# Keys.net
KiCad netlist of a schematic drawn in Altium Designer
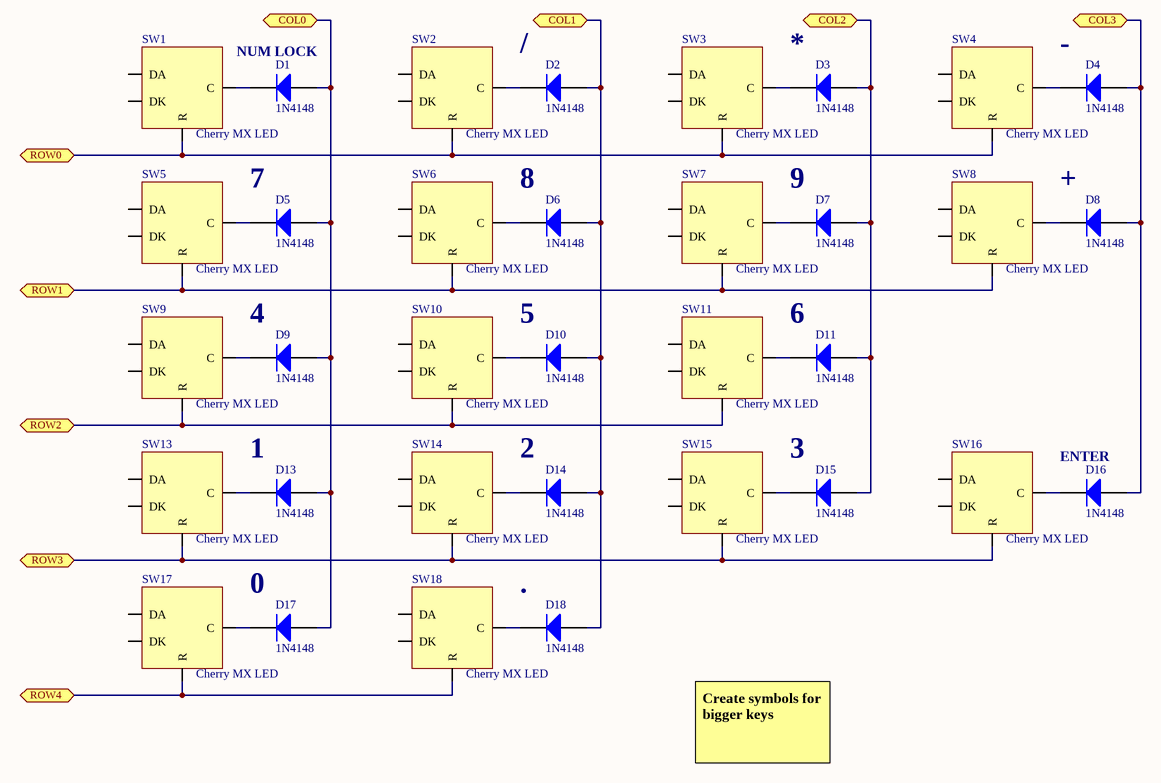
[diagram p0: Keys.SchDoc]

(export (version "E")
  (design (tool "Eeschema 10.0.6"))
  (components
    (comp (ref "D1")
      (value "1N4148")
      (footprint "NXP-SOD27-2_V")
      (description "High-speed Diode, 100 V, 450 mA, 2-Pin SOD27, RoHS")
      (fields (field (name "MANUFACTURER") "NXP Semiconductors"))
      (libsource (lib "Altium Content Vault") (part "NXP-A1K2-2"))
    )
    (comp (ref "D2")
      (value "1N4148")
      (footprint "NXP-SOD27-2_V")
      (description "High-speed Diode, 100 V, 450 mA, 2-Pin SOD27, RoHS")
      (fields (field (name "MANUFACTURER") "NXP Semiconductors"))
      (libsource (lib "Altium Content Vault") (part "NXP-A1K2-2"))
    )
    (comp (ref "D3")
      (value "1N4148")
      (footprint "NXP-SOD27-2_V")
      (description "High-speed Diode, 100 V, 450 mA, 2-Pin SOD27, RoHS")
      (fields (field (name "MANUFACTURER") "NXP Semiconductors"))
      (libsource (lib "Altium Content Vault") (part "NXP-A1K2-2"))
    )
    (comp (ref "D4")
      (value "1N4148")
      (footprint "NXP-SOD27-2_V")
      (description "High-speed Diode, 100 V, 450 mA, 2-Pin SOD27, RoHS")
      (fields (field (name "MANUFACTURER") "NXP Semiconductors"))
      (libsource (lib "Altium Content Vault") (part "NXP-A1K2-2"))
    )
    (comp (ref "D5")
      (value "1N4148")
      (footprint "NXP-SOD27-2_V")
      (description "High-speed Diode, 100 V, 450 mA, 2-Pin SOD27, RoHS")
      (fields (field (name "MANUFACTURER") "NXP Semiconductors"))
      (libsource (lib "Altium Content Vault") (part "NXP-A1K2-2"))
    )
    (comp (ref "D6")
      (value "1N4148")
      (footprint "NXP-SOD27-2_V")
      (description "High-speed Diode, 100 V, 450 mA, 2-Pin SOD27, RoHS")
      (fields (field (name "MANUFACTURER") "NXP Semiconductors"))
      (libsource (lib "Altium Content Vault") (part "NXP-A1K2-2"))
    )
    (comp (ref "D7")
      (value "1N4148")
      (footprint "NXP-SOD27-2_V")
      (description "High-speed Diode, 100 V, 450 mA, 2-Pin SOD27, RoHS")
      (fields (field (name "MANUFACTURER") "NXP Semiconductors"))
      (libsource (lib "Altium Content Vault") (part "NXP-A1K2-2"))
    )
    (comp (ref "D8")
      (value "1N4148")
      (footprint "NXP-SOD27-2_V")
      (description "High-speed Diode, 100 V, 450 mA, 2-Pin SOD27, RoHS")
      (fields (field (name "MANUFACTURER") "NXP Semiconductors"))
      (libsource (lib "Altium Content Vault") (part "NXP-A1K2-2"))
    )
    (comp (ref "D9")
      (value "1N4148")
      (footprint "NXP-SOD27-2_V")
      (description "High-speed Diode, 100 V, 450 mA, 2-Pin SOD27, RoHS")
      (fields (field (name "MANUFACTURER") "NXP Semiconductors"))
      (libsource (lib "Altium Content Vault") (part "NXP-A1K2-2"))
    )
    (comp (ref "D10")
      (value "1N4148")
      (footprint "NXP-SOD27-2_V")
      (description "High-speed Diode, 100 V, 450 mA, 2-Pin SOD27, RoHS")
      (fields (field (name "MANUFACTURER") "NXP Semiconductors"))
      (libsource (lib "Altium Content Vault") (part "NXP-A1K2-2"))
    )
    (comp (ref "D11")
      (value "1N4148")
      (footprint "NXP-SOD27-2_V")
      (description "High-speed Diode, 100 V, 450 mA, 2-Pin SOD27, RoHS")
      (fields (field (name "MANUFACTURER") "NXP Semiconductors"))
      (libsource (lib "Altium Content Vault") (part "NXP-A1K2-2"))
    )
    (comp (ref "D13")
      (value "1N4148")
      (footprint "NXP-SOD27-2_V")
      (description "High-speed Diode, 100 V, 450 mA, 2-Pin SOD27, RoHS")
      (fields (field (name "MANUFACTURER") "NXP Semiconductors"))
      (libsource (lib "Altium Content Vault") (part "NXP-A1K2-2"))
    )
    (comp (ref "D14")
      (value "1N4148")
      (footprint "NXP-SOD27-2_V")
      (description "High-speed Diode, 100 V, 450 mA, 2-Pin SOD27, RoHS")
      (fields (field (name "MANUFACTURER") "NXP Semiconductors"))
      (libsource (lib "Altium Content Vault") (part "NXP-A1K2-2"))
    )
    (comp (ref "D15")
      (value "1N4148")
      (footprint "NXP-SOD27-2_V")
      (description "High-speed Diode, 100 V, 450 mA, 2-Pin SOD27, RoHS")
      (fields (field (name "MANUFACTURER") "NXP Semiconductors"))
      (libsource (lib "Altium Content Vault") (part "NXP-A1K2-2"))
    )
    (comp (ref "D16")
      (value "1N4148")
      (footprint "NXP-SOD27-2_V")
      (description "High-speed Diode, 100 V, 450 mA, 2-Pin SOD27, RoHS")
      (fields (field (name "MANUFACTURER") "NXP Semiconductors"))
      (libsource (lib "Altium Content Vault") (part "NXP-A1K2-2"))
    )
    (comp (ref "D17")
      (value "1N4148")
      (footprint "NXP-SOD27-2_V")
      (description "High-speed Diode, 100 V, 450 mA, 2-Pin SOD27, RoHS")
      (fields (field (name "MANUFACTURER") "NXP Semiconductors"))
      (libsource (lib "Altium Content Vault") (part "NXP-A1K2-2"))
    )
    (comp (ref "D18")
      (value "1N4148")
      (footprint "NXP-SOD27-2_V")
      (description "High-speed Diode, 100 V, 450 mA, 2-Pin SOD27, RoHS")
      (fields (field (name "MANUFACTURER") "NXP Semiconductors"))
      (libsource (lib "Altium Content Vault") (part "NXP-A1K2-2"))
    )
    (comp (ref "SW1")
      (value "Cherry MX LED")
      (footprint "Cherry MX LED")
      (libsource (lib "Cherry MX") (part "Cherry MX LED"))
    )
    (comp (ref "SW2")
      (value "Cherry MX LED")
      (footprint "Cherry MX LED")
      (libsource (lib "Cherry MX") (part "Cherry MX LED"))
    )
    (comp (ref "SW3")
      (value "Cherry MX LED")
      (footprint "Cherry MX LED")
      (libsource (lib "Cherry MX") (part "Cherry MX LED"))
    )
    (comp (ref "SW4")
      (value "Cherry MX LED")
      (footprint "Cherry MX LED")
      (libsource (lib "Cherry MX") (part "Cherry MX LED"))
    )
    (comp (ref "SW5")
      (value "Cherry MX LED")
      (footprint "Cherry MX LED")
      (libsource (lib "Cherry MX") (part "Cherry MX LED"))
    )
    (comp (ref "SW6")
      (value "Cherry MX LED")
      (footprint "Cherry MX LED")
      (libsource (lib "Cherry MX") (part "Cherry MX LED"))
    )
    (comp (ref "SW7")
      (value "Cherry MX LED")
      (footprint "Cherry MX LED")
      (libsource (lib "Cherry MX") (part "Cherry MX LED"))
    )
    (comp (ref "SW8")
      (value "Cherry MX LED")
      (footprint "Cherry MX LED")
      (libsource (lib "Cherry MX") (part "Cherry MX LED"))
    )
    (comp (ref "SW9")
      (value "Cherry MX LED")
      (footprint "Cherry MX LED")
      (libsource (lib "Cherry MX") (part "Cherry MX LED"))
    )
    (comp (ref "SW10")
      (value "Cherry MX LED")
      (footprint "Cherry MX LED")
      (libsource (lib "Cherry MX") (part "Cherry MX LED"))
    )
    (comp (ref "SW11")
      (value "Cherry MX LED")
      (footprint "Cherry MX LED")
      (libsource (lib "Cherry MX") (part "Cherry MX LED"))
    )
    (comp (ref "SW13")
      (value "Cherry MX LED")
      (footprint "Cherry MX LED")
      (libsource (lib "Cherry MX") (part "Cherry MX LED"))
    )
    (comp (ref "SW14")
      (value "Cherry MX LED")
      (footprint "Cherry MX LED")
      (libsource (lib "Cherry MX") (part "Cherry MX LED"))
    )
    (comp (ref "SW15")
      (value "Cherry MX LED")
      (footprint "Cherry MX LED")
      (libsource (lib "Cherry MX") (part "Cherry MX LED"))
    )
    (comp (ref "SW16")
      (value "Cherry MX LED")
      (footprint "Cherry MX LED")
      (libsource (lib "Cherry MX") (part "Cherry MX LED"))
    )
    (comp (ref "SW17")
      (value "Cherry MX LED")
      (footprint "Cherry MX LED")
      (libsource (lib "Cherry MX") (part "Cherry MX LED"))
    )
    (comp (ref "SW18")
      (value "Cherry MX LED")
      (footprint "Cherry MX LED")
      (libsource (lib "Cherry MX") (part "Cherry MX LED"))
    )
  )
  (nets
    (net (code "1") (name "/COL0") (class "Default")
      (node (ref "D1") (pin "1") (pinfunction "A_1") (pintype "passive"))
      (node (ref "D13") (pin "1") (pinfunction "A_1") (pintype "passive"))
      (node (ref "D17") (pin "1") (pinfunction "A_1") (pintype "passive"))
      (node (ref "D5") (pin "1") (pinfunction "A_1") (pintype "passive"))
      (node (ref "D9") (pin "1") (pinfunction "A_1") (pintype "passive"))
    )
    (net (code "2") (name "/COL1") (class "Default")
      (node (ref "D10") (pin "1") (pinfunction "A_1") (pintype "passive"))
      (node (ref "D14") (pin "1") (pinfunction "A_1") (pintype "passive"))
      (node (ref "D18") (pin "1") (pinfunction "A_1") (pintype "passive"))
      (node (ref "D2") (pin "1") (pinfunction "A_1") (pintype "passive"))
      (node (ref "D6") (pin "1") (pinfunction "A_1") (pintype "passive"))
    )
    (net (code "3") (name "/COL2") (class "Default")
      (node (ref "D11") (pin "1") (pinfunction "A_1") (pintype "passive"))
      (node (ref "D15") (pin "1") (pinfunction "A_1") (pintype "passive"))
      (node (ref "D3") (pin "1") (pinfunction "A_1") (pintype "passive"))
      (node (ref "D7") (pin "1") (pinfunction "A_1") (pintype "passive"))
    )
    (net (code "4") (name "/COL3") (class "Default")
      (node (ref "D16") (pin "1") (pinfunction "A_1") (pintype "passive"))
      (node (ref "D4") (pin "1") (pinfunction "A_1") (pintype "passive"))
      (node (ref "D8") (pin "1") (pinfunction "A_1") (pintype "passive"))
    )
    (net (code "5") (name "/ROW0") (class "Default")
      (node (ref "SW1") (pin "1") (pinfunction "R_1") (pintype "passive"))
      (node (ref "SW2") (pin "1") (pinfunction "R_1") (pintype "passive"))
      (node (ref "SW3") (pin "1") (pinfunction "R_1") (pintype "passive"))
      (node (ref "SW4") (pin "1") (pinfunction "R_1") (pintype "passive"))
    )
    (net (code "6") (name "/ROW1") (class "Default")
      (node (ref "SW5") (pin "1") (pinfunction "R_1") (pintype "passive"))
      (node (ref "SW6") (pin "1") (pinfunction "R_1") (pintype "passive"))
      (node (ref "SW7") (pin "1") (pinfunction "R_1") (pintype "passive"))
      (node (ref "SW8") (pin "1") (pinfunction "R_1") (pintype "passive"))
    )
    (net (code "7") (name "/ROW2") (class "Default")
      (node (ref "SW10") (pin "1") (pinfunction "R_1") (pintype "passive"))
      (node (ref "SW11") (pin "1") (pinfunction "R_1") (pintype "passive"))
      (node (ref "SW9") (pin "1") (pinfunction "R_1") (pintype "passive"))
    )
    (net (code "8") (name "/ROW3") (class "Default")
      (node (ref "SW13") (pin "1") (pinfunction "R_1") (pintype "passive"))
      (node (ref "SW14") (pin "1") (pinfunction "R_1") (pintype "passive"))
      (node (ref "SW15") (pin "1") (pinfunction "R_1") (pintype "passive"))
      (node (ref "SW16") (pin "1") (pinfunction "R_1") (pintype "passive"))
    )
    (net (code "9") (name "/ROW4") (class "Default")
      (node (ref "SW17") (pin "1") (pinfunction "R_1") (pintype "passive"))
      (node (ref "SW18") (pin "1") (pinfunction "R_1") (pintype "passive"))
    )
    (net (code "10") (name "Net-(D1-K)") (class "Default")
      (node (ref "D1") (pin "2") (pinfunction "K_2") (pintype "passive"))
      (node (ref "SW1") (pin "2") (pinfunction "C_2") (pintype "passive"))
    )
    (net (code "11") (name "Net-(D2-K)") (class "Default")
      (node (ref "D2") (pin "2") (pinfunction "K_2") (pintype "passive"))
      (node (ref "SW2") (pin "2") (pinfunction "C_2") (pintype "passive"))
    )
    (net (code "12") (name "Net-(D3-K)") (class "Default")
      (node (ref "D3") (pin "2") (pinfunction "K_2") (pintype "passive"))
      (node (ref "SW3") (pin "2") (pinfunction "C_2") (pintype "passive"))
    )
    (net (code "13") (name "Net-(D4-K)") (class "Default")
      (node (ref "D4") (pin "2") (pinfunction "K_2") (pintype "passive"))
      (node (ref "SW4") (pin "2") (pinfunction "C_2") (pintype "passive"))
    )
    (net (code "14") (name "Net-(D5-K)") (class "Default")
      (node (ref "D5") (pin "2") (pinfunction "K_2") (pintype "passive"))
      (node (ref "SW5") (pin "2") (pinfunction "C_2") (pintype "passive"))
    )
    (net (code "15") (name "Net-(D6-K)") (class "Default")
      (node (ref "D6") (pin "2") (pinfunction "K_2") (pintype "passive"))
      (node (ref "SW6") (pin "2") (pinfunction "C_2") (pintype "passive"))
    )
    (net (code "16") (name "Net-(D7-K)") (class "Default")
      (node (ref "D7") (pin "2") (pinfunction "K_2") (pintype "passive"))
      (node (ref "SW7") (pin "2") (pinfunction "C_2") (pintype "passive"))
    )
    (net (code "17") (name "Net-(D8-K)") (class "Default")
      (node (ref "D8") (pin "2") (pinfunction "K_2") (pintype "passive"))
      (node (ref "SW8") (pin "2") (pinfunction "C_2") (pintype "passive"))
    )
    (net (code "18") (name "Net-(D9-K)") (class "Default")
      (node (ref "D9") (pin "2") (pinfunction "K_2") (pintype "passive"))
      (node (ref "SW9") (pin "2") (pinfunction "C_2") (pintype "passive"))
    )
    (net (code "19") (name "Net-(D10-K)") (class "Default")
      (node (ref "D10") (pin "2") (pinfunction "K_2") (pintype "passive"))
      (node (ref "SW10") (pin "2") (pinfunction "C_2") (pintype "passive"))
    )
    (net (code "20") (name "Net-(D11-K)") (class "Default")
      (node (ref "D11") (pin "2") (pinfunction "K_2") (pintype "passive"))
      (node (ref "SW11") (pin "2") (pinfunction "C_2") (pintype "passive"))
    )
    (net (code "21") (name "Net-(D13-K)") (class "Default")
      (node (ref "D13") (pin "2") (pinfunction "K_2") (pintype "passive"))
      (node (ref "SW13") (pin "2") (pinfunction "C_2") (pintype "passive"))
    )
    (net (code "22") (name "Net-(D14-K)") (class "Default")
      (node (ref "D14") (pin "2") (pinfunction "K_2") (pintype "passive"))
      (node (ref "SW14") (pin "2") (pinfunction "C_2") (pintype "passive"))
    )
    (net (code "23") (name "Net-(D15-K)") (class "Default")
      (node (ref "D15") (pin "2") (pinfunction "K_2") (pintype "passive"))
      (node (ref "SW15") (pin "2") (pinfunction "C_2") (pintype "passive"))
    )
    (net (code "24") (name "Net-(D16-K)") (class "Default")
      (node (ref "D16") (pin "2") (pinfunction "K_2") (pintype "passive"))
      (node (ref "SW16") (pin "2") (pinfunction "C_2") (pintype "passive"))
    )
    (net (code "25") (name "Net-(D17-K)") (class "Default")
      (node (ref "D17") (pin "2") (pinfunction "K_2") (pintype "passive"))
      (node (ref "SW17") (pin "2") (pinfunction "C_2") (pintype "passive"))
    )
    (net (code "26") (name "Net-(D18-K)") (class "Default")
      (node (ref "D18") (pin "2") (pinfunction "K_2") (pintype "passive"))
      (node (ref "SW18") (pin "2") (pinfunction "C_2") (pintype "passive"))
    )
    (net (code "27") (name "unconnected-(SW1-DA-Pad3)") (class "Default")
      (node (ref "SW1") (pin "3") (pinfunction "DA_3") (pintype "passive"))
    )
    (net (code "28") (name "unconnected-(SW1-DK-Pad4)") (class "Default")
      (node (ref "SW1") (pin "4") (pinfunction "DK_4") (pintype "passive"))
    )
    (net (code "29") (name "unconnected-(SW2-DA-Pad3)") (class "Default")
      (node (ref "SW2") (pin "3") (pinfunction "DA_3") (pintype "passive"))
    )
    (net (code "30") (name "unconnected-(SW2-DK-Pad4)") (class "Default")
      (node (ref "SW2") (pin "4") (pinfunction "DK_4") (pintype "passive"))
    )
    (net (code "31") (name "unconnected-(SW3-DA-Pad3)") (class "Default")
      (node (ref "SW3") (pin "3") (pinfunction "DA_3") (pintype "passive"))
    )
    (net (code "32") (name "unconnected-(SW3-DK-Pad4)") (class "Default")
      (node (ref "SW3") (pin "4") (pinfunction "DK_4") (pintype "passive"))
    )
    (net (code "33") (name "unconnected-(SW4-DA-Pad3)") (class "Default")
      (node (ref "SW4") (pin "3") (pinfunction "DA_3") (pintype "passive"))
    )
    (net (code "34") (name "unconnected-(SW4-DK-Pad4)") (class "Default")
      (node (ref "SW4") (pin "4") (pinfunction "DK_4") (pintype "passive"))
    )
    (net (code "35") (name "unconnected-(SW5-DA-Pad3)") (class "Default")
      (node (ref "SW5") (pin "3") (pinfunction "DA_3") (pintype "passive"))
    )
    (net (code "36") (name "unconnected-(SW5-DK-Pad4)") (class "Default")
      (node (ref "SW5") (pin "4") (pinfunction "DK_4") (pintype "passive"))
    )
    (net (code "37") (name "unconnected-(SW6-DA-Pad3)") (class "Default")
      (node (ref "SW6") (pin "3") (pinfunction "DA_3") (pintype "passive"))
    )
    (net (code "38") (name "unconnected-(SW6-DK-Pad4)") (class "Default")
      (node (ref "SW6") (pin "4") (pinfunction "DK_4") (pintype "passive"))
    )
    (net (code "39") (name "unconnected-(SW7-DA-Pad3)") (class "Default")
      (node (ref "SW7") (pin "3") (pinfunction "DA_3") (pintype "passive"))
    )
    (net (code "40") (name "unconnected-(SW7-DK-Pad4)") (class "Default")
      (node (ref "SW7") (pin "4") (pinfunction "DK_4") (pintype "passive"))
    )
    (net (code "41") (name "unconnected-(SW8-DA-Pad3)") (class "Default")
      (node (ref "SW8") (pin "3") (pinfunction "DA_3") (pintype "passive"))
    )
    (net (code "42") (name "unconnected-(SW8-DK-Pad4)") (class "Default")
      (node (ref "SW8") (pin "4") (pinfunction "DK_4") (pintype "passive"))
    )
    (net (code "43") (name "unconnected-(SW9-DA-Pad3)") (class "Default")
      (node (ref "SW9") (pin "3") (pinfunction "DA_3") (pintype "passive"))
    )
    (net (code "44") (name "unconnected-(SW9-DK-Pad4)") (class "Default")
      (node (ref "SW9") (pin "4") (pinfunction "DK_4") (pintype "passive"))
    )
    (net (code "45") (name "unconnected-(SW10-DA-Pad3)") (class "Default")
      (node (ref "SW10") (pin "3") (pinfunction "DA_3") (pintype "passive"))
    )
    (net (code "46") (name "unconnected-(SW10-DK-Pad4)") (class "Default")
      (node (ref "SW10") (pin "4") (pinfunction "DK_4") (pintype "passive"))
    )
    (net (code "47") (name "unconnected-(SW11-DA-Pad3)") (class "Default")
      (node (ref "SW11") (pin "3") (pinfunction "DA_3") (pintype "passive"))
    )
    (net (code "48") (name "unconnected-(SW11-DK-Pad4)") (class "Default")
      (node (ref "SW11") (pin "4") (pinfunction "DK_4") (pintype "passive"))
    )
    (net (code "49") (name "unconnected-(SW13-DA-Pad3)") (class "Default")
      (node (ref "SW13") (pin "3") (pinfunction "DA_3") (pintype "passive"))
    )
    (net (code "50") (name "unconnected-(SW13-DK-Pad4)") (class "Default")
      (node (ref "SW13") (pin "4") (pinfunction "DK_4") (pintype "passive"))
    )
    (net (code "51") (name "unconnected-(SW14-DA-Pad3)") (class "Default")
      (node (ref "SW14") (pin "3") (pinfunction "DA_3") (pintype "passive"))
    )
    (net (code "52") (name "unconnected-(SW14-DK-Pad4)") (class "Default")
      (node (ref "SW14") (pin "4") (pinfunction "DK_4") (pintype "passive"))
    )
    (net (code "53") (name "unconnected-(SW15-DA-Pad3)") (class "Default")
      (node (ref "SW15") (pin "3") (pinfunction "DA_3") (pintype "passive"))
    )
    (net (code "54") (name "unconnected-(SW15-DK-Pad4)") (class "Default")
      (node (ref "SW15") (pin "4") (pinfunction "DK_4") (pintype "passive"))
    )
    (net (code "55") (name "unconnected-(SW16-DA-Pad3)") (class "Default")
      (node (ref "SW16") (pin "3") (pinfunction "DA_3") (pintype "passive"))
    )
    (net (code "56") (name "unconnected-(SW16-DK-Pad4)") (class "Default")
      (node (ref "SW16") (pin "4") (pinfunction "DK_4") (pintype "passive"))
    )
    (net (code "57") (name "unconnected-(SW17-DA-Pad3)") (class "Default")
      (node (ref "SW17") (pin "3") (pinfunction "DA_3") (pintype "passive"))
    )
    (net (code "58") (name "unconnected-(SW17-DK-Pad4)") (class "Default")
      (node (ref "SW17") (pin "4") (pinfunction "DK_4") (pintype "passive"))
    )
    (net (code "59") (name "unconnected-(SW18-DA-Pad3)") (class "Default")
      (node (ref "SW18") (pin "3") (pinfunction "DA_3") (pintype "passive"))
    )
    (net (code "60") (name "unconnected-(SW18-DK-Pad4)") (class "Default")
      (node (ref "SW18") (pin "4") (pinfunction "DK_4") (pintype "passive"))
    )
  )
)
